# ArduBerry_5_0.net
KiCad netlist of a schematic drawn in EAGLE
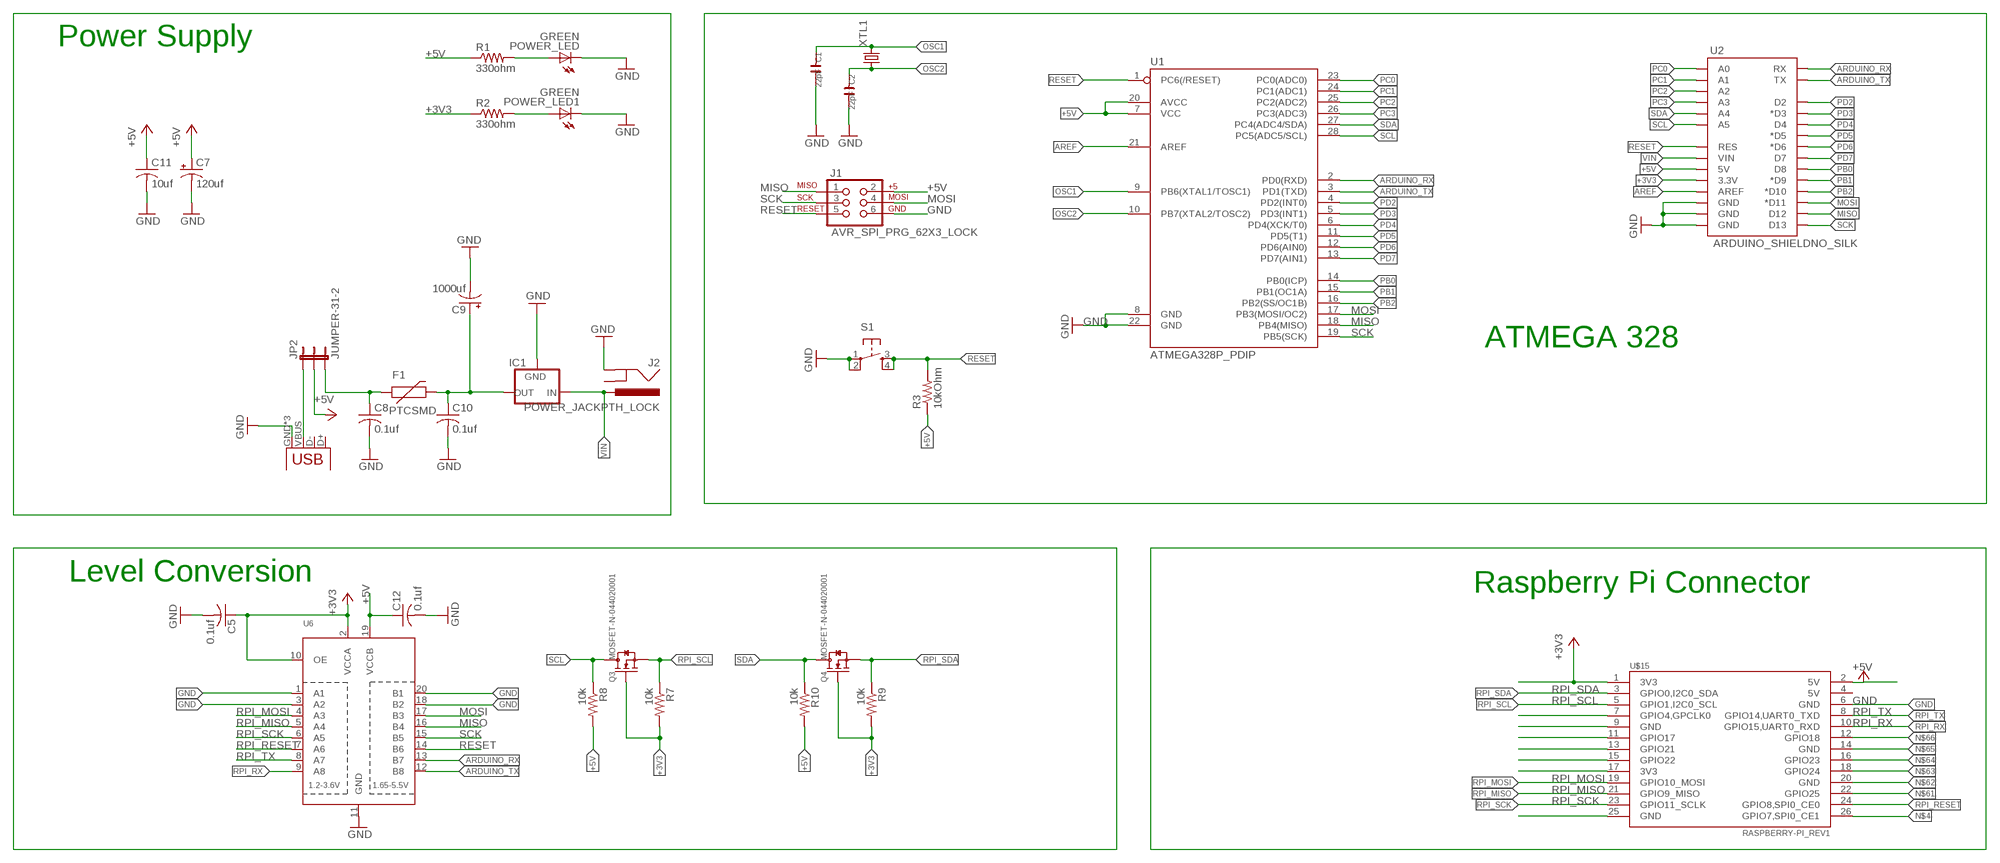
[diagram p0: schematic, sheet 1]

(export (version "E")
  (design (tool "Eeschema 10.0.6"))
  (components
    (comp (ref "C1")
      (value "22pF")
      (footprint "eagle-import:C0805")
      (libsource (lib "eagle-import") (part "C-0805"))
    )
    (comp (ref "C2")
      (value "22pF")
      (footprint "eagle-import:C0805")
      (libsource (lib "eagle-import") (part "C-0805"))
    )
    (comp (ref "C5")
      (value "0.1uf")
      (footprint "eagle-import:C0603")
      (libsource (lib "eagle-import") (part "resistor_C-USC0603"))
    )
    (comp (ref "C7")
      (value "120uf")
      (footprint "eagle-import:E2,5-6")
      (libsource (lib "eagle-import") (part "CPOL-USE2.5-6"))
    )
    (comp (ref "C8")
      (value "0.1uf")
      (footprint "eagle-import:C0603")
      (libsource (lib "eagle-import") (part "resistor_C-USC0603"))
    )
    (comp (ref "C9")
      (value "1000uf")
      (footprint "eagle-import:E3,5-10")
      (libsource (lib "eagle-import") (part "CPOL-USE3.5-10"))
    )
    (comp (ref "C10")
      (value "0.1uf")
      (footprint "eagle-import:C0603")
      (libsource (lib "eagle-import") (part "resistor_C-USC0603"))
    )
    (comp (ref "C11")
      (value "10uf")
      (footprint "eagle-import:C0805")
      (libsource (lib "eagle-import") (part "C-USC0805"))
    )
    (comp (ref "C12")
      (value "0.1uf")
      (footprint "eagle-import:C0603")
      (libsource (lib "eagle-import") (part "resistor_C-USC0603"))
    )
    (comp (ref "F1")
      (value "PTCSMD")
      (footprint "eagle-import:PTC-1206")
      (libsource (lib "eagle-import") (part "PTCSMD"))
    )
    (comp (ref "IC1")
      (value "V_REG_78XXSIDE")
      (footprint "eagle-import:78XXL")
      (libsource (lib "eagle-import") (part "V_REG_78XXSIDE"))
    )
    (comp (ref "J1")
      (value "AVR_SPI_PRG_62X3_LOCK")
      (footprint "eagle-import:2X3_LOCK")
      (libsource (lib "eagle-import") (part "AVR_SPI_PRG_62X3_LOCK"))
    )
    (comp (ref "J2")
      (value "POWER_JACKPTH_LOCK")
      (footprint "eagle-import:POWER_JACK_PTH_LOCK")
      (libsource (lib "eagle-import") (part "POWER_JACKPTH_LOCK"))
    )
    (comp (ref "JP1")
      (value "USB-MICROB")
      (footprint "eagle-import:USB-MICROB")
      (libsource (lib "eagle-import") (part "USB-MICROB"))
    )
    (comp (ref "JP2")
      (value "JUMPER-31-2")
      (footprint "eagle-import:SJ_3_PASTE1&2")
      (libsource (lib "eagle-import") (part "JUMPER-31-2"))
    )
    (comp (ref "POWER_LED")
      (value "GREEN")
      (footprint "eagle-import:LED-0603")
      (libsource (lib "eagle-import") (part "LED-GREEN0603"))
    )
    (comp (ref "POWER_LED1")
      (value "GREEN")
      (footprint "eagle-import:LED-0603")
      (libsource (lib "eagle-import") (part "LED-GREEN0603"))
    )
    (comp (ref "Q3")
      (value "MOSFET-N-044020001")
      (footprint "eagle-import:SOT23")
      (libsource (lib "eagle-import") (part "MOSFET-N-044020001"))
    )
    (comp (ref "Q4")
      (value "MOSFET-N-044020001")
      (footprint "eagle-import:SOT23")
      (libsource (lib "eagle-import") (part "MOSFET-N-044020001"))
    )
    (comp (ref "R1")
      (value "330ohm")
      (footprint "eagle-import:0603-RES")
      (libsource (lib "eagle-import") (part "RESISTOR0603"))
    )
    (comp (ref "R2")
      (value "330ohm")
      (footprint "eagle-import:0603-RES")
      (libsource (lib "eagle-import") (part "RESISTOR0603"))
    )
    (comp (ref "R3")
      (value "10kOhm")
      (footprint "eagle-import:0603-RES")
      (libsource (lib "eagle-import") (part "RESISTOR0603"))
    )
    (comp (ref "R7")
      (value "10k")
      (footprint "eagle-import:0603-RES")
      (libsource (lib "eagle-import") (part "RESISTOR0603"))
    )
    (comp (ref "R8")
      (value "10k")
      (footprint "eagle-import:0603-RES")
      (libsource (lib "eagle-import") (part "RESISTOR0603"))
    )
    (comp (ref "R9")
      (value "10k")
      (footprint "eagle-import:0603-RES")
      (libsource (lib "eagle-import") (part "RESISTOR0603"))
    )
    (comp (ref "R10")
      (value "10k")
      (footprint "eagle-import:0603-RES")
      (libsource (lib "eagle-import") (part "RESISTOR0603"))
    )
    (comp (ref "S1")
      (value "TAC_SWITCHPTH")
      (footprint "eagle-import:TACTILE-PTH")
      (libsource (lib "eagle-import") (part "TAC_SWITCHPTH"))
    )
    (comp (ref "U$15")
      (value "RASPBERRY-PI_REV1")
      (footprint "eagle-import:RASPBERRY-PI_REV1")
      (libsource (lib "eagle-import") (part "RASPBERRY-PI_REV1"))
    )
    (comp (ref "U1")
      (value "ATMEGA328P_PDIP")
      (footprint "eagle-import:DIL28-3")
      (libsource (lib "eagle-import") (part "ATMEGA328P_PDIP"))
    )
    (comp (ref "U2")
      (value "ARDUINO_SHIELDNO_SILK")
      (footprint "eagle-import:DUEMILANOVE_VIAS")
      (libsource (lib "eagle-import") (part "ARDUINO_SHIELDNO_SILK"))
    )
    (comp (ref "U6")
      (value "TXB0108PWR")
      (footprint "eagle-import:TSSOP20")
      (libsource (lib "eagle-import") (part "TXB0108PWR"))
    )
    (comp (ref "XTL1")
      (value "CRYSTALHC49S")
      (footprint "eagle-import:HC49_S")
      (libsource (lib "eagle-import") (part "CRYSTALHC49S"))
    )
  )
  (nets
    (net (code "1") (name "+3V3") (class "Default")
      (node (ref "C5") (pin "1") (pinfunction "1_1") (pintype "passive"))
      (node (ref "Q3") (pin "1") (pinfunction "G_1") (pintype "passive"))
      (node (ref "Q4") (pin "1") (pinfunction "G_1") (pintype "passive"))
      (node (ref "R2") (pin "1") (pinfunction "1_1") (pintype "passive"))
      (node (ref "R7") (pin "2") (pinfunction "2_2") (pintype "passive"))
      (node (ref "R9") (pin "2") (pinfunction "2_2") (pintype "passive"))
      (node (ref "U$15") (pin "1") (pinfunction "3V3_1") (pintype "bidirectional"))
      (node (ref "U2") (pin "3.3V") (pinfunction "3.3V_3.3V") (pintype "bidirectional"))
      (node (ref "U6") (pin "10") (pinfunction "OE_10") (pintype "bidirectional"))
      (node (ref "U6") (pin "2") (pinfunction "VCCA_2") (pintype "bidirectional"))
    )
    (net (code "2") (name "+5V") (class "Default")
      (node (ref "C11") (pin "1") (pinfunction "1_1") (pintype "passive"))
      (node (ref "C12") (pin "1") (pinfunction "1_1") (pintype "passive"))
      (node (ref "C7") (pin "+") (pinfunction "+_+") (pintype "passive"))
      (node (ref "J1") (pin "2") (pinfunction "2_2") (pintype "passive"))
      (node (ref "JP2") (pin "2") (pinfunction "2_2") (pintype "passive"))
      (node (ref "R1") (pin "1") (pinfunction "1_1") (pintype "passive"))
      (node (ref "R10") (pin "2") (pinfunction "2_2") (pintype "passive"))
      (node (ref "R3") (pin "1") (pinfunction "1_1") (pintype "passive"))
      (node (ref "R8") (pin "2") (pinfunction "2_2") (pintype "passive"))
      (node (ref "U$15") (pin "2") (pinfunction "5V_2") (pintype "bidirectional"))
      (node (ref "U1") (pin "20") (pinfunction "AVCC_20") (pintype "bidirectional"))
      (node (ref "U1") (pin "7") (pinfunction "VCC_7") (pintype "bidirectional"))
      (node (ref "U2") (pin "5V") (pinfunction "5V_5V") (pintype "bidirectional"))
      (node (ref "U6") (pin "19") (pinfunction "VCCB_19") (pintype "bidirectional"))
    )
    (net (code "3") (name "ARDUINO_RX") (class "Default")
      (node (ref "U1") (pin "2") (pinfunction "PD0(RXD)_2") (pintype "bidirectional"))
      (node (ref "U2") (pin "RX") (pinfunction "RX_RX") (pintype "bidirectional"))
      (node (ref "U6") (pin "13") (pinfunction "B7_13") (pintype "bidirectional"))
    )
    (net (code "4") (name "ARDUINO_TX") (class "Default")
      (node (ref "U1") (pin "3") (pinfunction "PD1(TXD)_3") (pintype "bidirectional"))
      (node (ref "U2") (pin "TX") (pinfunction "TX_TX") (pintype "bidirectional"))
      (node (ref "U6") (pin "12") (pinfunction "B8_12") (pintype "bidirectional"))
    )
    (net (code "5") (name "AREF") (class "Default")
      (node (ref "U1") (pin "21") (pinfunction "AREF_21") (pintype "bidirectional"))
      (node (ref "U2") (pin "AREF") (pinfunction "AREF_AREF") (pintype "bidirectional"))
    )
    (net (code "6") (name "GND") (class "Default")
      (node (ref "C1") (pin "2") (pinfunction "2_2") (pintype "bidirectional"))
      (node (ref "C10") (pin "2") (pinfunction "2_2") (pintype "passive"))
      (node (ref "C11") (pin "2") (pinfunction "2_2") (pintype "passive"))
      (node (ref "C12") (pin "2") (pinfunction "2_2") (pintype "passive"))
      (node (ref "C2") (pin "2") (pinfunction "2_2") (pintype "bidirectional"))
      (node (ref "C5") (pin "2") (pinfunction "2_2") (pintype "passive"))
      (node (ref "C7") (pin "-") (pinfunction "-_-") (pintype "passive"))
      (node (ref "C8") (pin "2") (pinfunction "2_2") (pintype "passive"))
      (node (ref "C9") (pin "-") (pinfunction "-_-") (pintype "passive"))
      (node (ref "IC1") (pin "GND") (pinfunction "GND_GND") (pintype "input"))
      (node (ref "J1") (pin "6") (pinfunction "6_6") (pintype "passive"))
      (node (ref "J2") (pin "GND") (pinfunction "GND_GND") (pintype "bidirectional"))
      (node (ref "JP1") (pin "GND") (pinfunction "GND_GND") (pintype "bidirectional"))
      (node (ref "JP1") (pin "MT1") (pinfunction "GND_MT1") (pintype "bidirectional"))
      (node (ref "JP1") (pin "MT2") (pinfunction "GND_MT2") (pintype "bidirectional"))
      (node (ref "POWER_LED") (pin "C") (pinfunction "C_C") (pintype "passive"))
      (node (ref "POWER_LED1") (pin "C") (pinfunction "C_C") (pintype "passive"))
      (node (ref "S1") (pin "1") (pinfunction "1_1") (pintype "passive"))
      (node (ref "S1") (pin "2") (pinfunction "2_2") (pintype "passive"))
      (node (ref "U$15") (pin "6") (pinfunction "GND_6") (pintype "bidirectional"))
      (node (ref "U1") (pin "22") (pinfunction "GND_22") (pintype "bidirectional"))
      (node (ref "U1") (pin "8") (pinfunction "GND_8") (pintype "bidirectional"))
      (node (ref "U2") (pin "GND@0") (pinfunction "GND_GND@0") (pintype "bidirectional"))
      (node (ref "U2") (pin "GND@1") (pinfunction "GND_GND@1") (pintype "bidirectional"))
      (node (ref "U2") (pin "GND@2") (pinfunction "GND_GND@2") (pintype "bidirectional"))
      (node (ref "U6") (pin "1") (pinfunction "A1_1") (pintype "bidirectional"))
      (node (ref "U6") (pin "11") (pinfunction "GND_11") (pintype "bidirectional"))
      (node (ref "U6") (pin "18") (pinfunction "B2_18") (pintype "bidirectional"))
      (node (ref "U6") (pin "20") (pinfunction "B1_20") (pintype "bidirectional"))
      (node (ref "U6") (pin "3") (pinfunction "A2_3") (pintype "bidirectional"))
    )
    (net (code "7") (name "MISO") (class "Default")
      (node (ref "J1") (pin "1") (pinfunction "1_1") (pintype "passive"))
      (node (ref "U1") (pin "18") (pinfunction "PB4(MISO)_18") (pintype "bidirectional"))
      (node (ref "U2") (pin "D12") (pinfunction "D12_D12") (pintype "bidirectional"))
      (node (ref "U6") (pin "16") (pinfunction "B4_16") (pintype "bidirectional"))
    )
    (net (code "8") (name "MOSI") (class "Default")
      (node (ref "J1") (pin "4") (pinfunction "4_4") (pintype "passive"))
      (node (ref "U1") (pin "17") (pinfunction "PB3(MOSI/OC2)_17") (pintype "bidirectional"))
      (node (ref "U2") (pin "D11") (pinfunction "*D11_D11") (pintype "bidirectional"))
      (node (ref "U6") (pin "17") (pinfunction "B3_17") (pintype "bidirectional"))
    )
    (net (code "9") (name "N$4") (class "Default")
      (node (ref "U$15") (pin "26") (pinfunction "GPIO7,SPI0_CE1_26") (pintype "bidirectional"))
    )
    (net (code "10") (name "N$61") (class "Default")
      (node (ref "U$15") (pin "22") (pinfunction "GPIO25_22") (pintype "bidirectional"))
    )
    (net (code "11") (name "N$62") (class "Default")
      (node (ref "U$15") (pin "20") (pinfunction "GND_20") (pintype "bidirectional"))
    )
    (net (code "12") (name "N$63") (class "Default")
      (node (ref "U$15") (pin "18") (pinfunction "GPIO24_18") (pintype "bidirectional"))
    )
    (net (code "13") (name "N$64") (class "Default")
      (node (ref "U$15") (pin "16") (pinfunction "GPIO23_16") (pintype "bidirectional"))
    )
    (net (code "14") (name "N$65") (class "Default")
      (node (ref "U$15") (pin "14") (pinfunction "GND_14") (pintype "bidirectional"))
    )
    (net (code "15") (name "N$66") (class "Default")
      (node (ref "U$15") (pin "12") (pinfunction "GPIO18_12") (pintype "bidirectional"))
    )
    (net (code "16") (name "Net-(C8-Pad1)") (class "Default")
      (node (ref "C8") (pin "1") (pinfunction "1_1") (pintype "passive"))
      (node (ref "F1") (pin "1") (pinfunction "1_1") (pintype "bidirectional"))
      (node (ref "JP2") (pin "3") (pinfunction "3_3") (pintype "passive"))
    )
    (net (code "17") (name "Net-(C10-Pad1)") (class "Default")
      (node (ref "C10") (pin "1") (pinfunction "1_1") (pintype "passive"))
      (node (ref "C9") (pin "+") (pinfunction "+_+") (pintype "passive"))
      (node (ref "F1") (pin "2") (pinfunction "2_2") (pintype "bidirectional"))
      (node (ref "IC1") (pin "OUT") (pinfunction "OUT_OUT") (pintype "output"))
    )
    (net (code "18") (name "Net-(JP1-PadVBUS)") (class "Default")
      (node (ref "JP1") (pin "VBUS") (pinfunction "VBUS_VBUS") (pintype "bidirectional"))
      (node (ref "JP2") (pin "1") (pinfunction "1_1") (pintype "passive"))
    )
    (net (code "19") (name "Net-(POWER_LED-PadA)") (class "Default")
      (node (ref "POWER_LED") (pin "A") (pinfunction "A_A") (pintype "passive"))
      (node (ref "R1") (pin "2") (pinfunction "2_2") (pintype "passive"))
    )
    (net (code "20") (name "Net-(POWER_LED1-PadA)") (class "Default")
      (node (ref "POWER_LED1") (pin "A") (pinfunction "A_A") (pintype "passive"))
      (node (ref "R2") (pin "2") (pinfunction "2_2") (pintype "passive"))
    )
    (net (code "21") (name "OSC1") (class "Default")
      (node (ref "C1") (pin "1") (pinfunction "1_1") (pintype "bidirectional"))
      (node (ref "U1") (pin "9") (pinfunction "PB6(XTAL1/TOSC1)_9") (pintype "bidirectional"))
      (node (ref "XTL1") (pin "2") (pinfunction "2_2") (pintype "passive"))
    )
    (net (code "22") (name "OSC2") (class "Default")
      (node (ref "C2") (pin "1") (pinfunction "1_1") (pintype "bidirectional"))
      (node (ref "U1") (pin "10") (pinfunction "PB7(XTAL2/TOSC2)_10") (pintype "bidirectional"))
      (node (ref "XTL1") (pin "1") (pinfunction "1_1") (pintype "passive"))
    )
    (net (code "23") (name "PB0") (class "Default")
      (node (ref "U1") (pin "14") (pinfunction "PB0(ICP)_14") (pintype "bidirectional"))
      (node (ref "U2") (pin "D8") (pinfunction "D8_D8") (pintype "bidirectional"))
    )
    (net (code "24") (name "PB1") (class "Default")
      (node (ref "U1") (pin "15") (pinfunction "PB1(OC1A)_15") (pintype "bidirectional"))
      (node (ref "U2") (pin "D9") (pinfunction "*D9_D9") (pintype "bidirectional"))
    )
    (net (code "25") (name "PB2") (class "Default")
      (node (ref "U1") (pin "16") (pinfunction "PB2(SS/OC1B)_16") (pintype "bidirectional"))
      (node (ref "U2") (pin "D10") (pinfunction "*D10_D10") (pintype "bidirectional"))
    )
    (net (code "26") (name "PC0") (class "Default")
      (node (ref "U1") (pin "23") (pinfunction "PC0(ADC0)_23") (pintype "bidirectional"))
      (node (ref "U2") (pin "A0") (pinfunction "A0_A0") (pintype "bidirectional"))
    )
    (net (code "27") (name "PC1") (class "Default")
      (node (ref "U1") (pin "24") (pinfunction "PC1(ADC1)_24") (pintype "bidirectional"))
      (node (ref "U2") (pin "A1") (pinfunction "A1_A1") (pintype "bidirectional"))
    )
    (net (code "28") (name "PC2") (class "Default")
      (node (ref "U1") (pin "25") (pinfunction "PC2(ADC2)_25") (pintype "bidirectional"))
      (node (ref "U2") (pin "A2") (pinfunction "A2_A2") (pintype "bidirectional"))
    )
    (net (code "29") (name "PC3") (class "Default")
      (node (ref "U1") (pin "26") (pinfunction "PC3(ADC3)_26") (pintype "bidirectional"))
      (node (ref "U2") (pin "A3") (pinfunction "A3_A3") (pintype "bidirectional"))
    )
    (net (code "30") (name "PD2") (class "Default")
      (node (ref "U1") (pin "4") (pinfunction "PD2(INT0)_4") (pintype "bidirectional"))
      (node (ref "U2") (pin "D2") (pinfunction "D2_D2") (pintype "bidirectional"))
    )
    (net (code "31") (name "PD3") (class "Default")
      (node (ref "U1") (pin "5") (pinfunction "PD3(INT1)_5") (pintype "bidirectional"))
      (node (ref "U2") (pin "D3") (pinfunction "*D3_D3") (pintype "bidirectional"))
    )
    (net (code "32") (name "PD4") (class "Default")
      (node (ref "U1") (pin "6") (pinfunction "PD4(XCK/T0)_6") (pintype "bidirectional"))
      (node (ref "U2") (pin "D4") (pinfunction "D4_D4") (pintype "bidirectional"))
    )
    (net (code "33") (name "PD5") (class "Default")
      (node (ref "U1") (pin "11") (pinfunction "PD5(T1)_11") (pintype "bidirectional"))
      (node (ref "U2") (pin "D5") (pinfunction "*D5_D5") (pintype "bidirectional"))
    )
    (net (code "34") (name "PD6") (class "Default")
      (node (ref "U1") (pin "12") (pinfunction "PD6(AIN0)_12") (pintype "bidirectional"))
      (node (ref "U2") (pin "D6") (pinfunction "*D6_D6") (pintype "bidirectional"))
    )
    (net (code "35") (name "PD7") (class "Default")
      (node (ref "U1") (pin "13") (pinfunction "PD7(AIN1)_13") (pintype "bidirectional"))
      (node (ref "U2") (pin "D7") (pinfunction "D7_D7") (pintype "bidirectional"))
    )
    (net (code "36") (name "RESET") (class "Default")
      (node (ref "J1") (pin "5") (pinfunction "5_5") (pintype "passive"))
      (node (ref "R3") (pin "2") (pinfunction "2_2") (pintype "passive"))
      (node (ref "S1") (pin "3") (pinfunction "3_3") (pintype "passive"))
      (node (ref "S1") (pin "4") (pinfunction "4_4") (pintype "passive"))
      (node (ref "U1") (pin "1") (pinfunction "PC6(/RESET)_1") (pintype "bidirectional"))
      (node (ref "U2") (pin "RES") (pinfunction "RES_RES") (pintype "bidirectional"))
      (node (ref "U6") (pin "14") (pinfunction "B6_14") (pintype "bidirectional"))
    )
    (net (code "37") (name "RPI_MISO") (class "Default")
      (node (ref "U$15") (pin "21") (pinfunction "GPIO9_MISO_21") (pintype "bidirectional"))
      (node (ref "U6") (pin "5") (pinfunction "A4_5") (pintype "bidirectional"))
    )
    (net (code "38") (name "RPI_MOSI") (class "Default")
      (node (ref "U$15") (pin "19") (pinfunction "GPIO10_MOSI_19") (pintype "bidirectional"))
      (node (ref "U6") (pin "4") (pinfunction "A3_4") (pintype "bidirectional"))
    )
    (net (code "39") (name "RPI_RESET") (class "Default")
      (node (ref "U$15") (pin "24") (pinfunction "GPIO8,SPI0_CE0_24") (pintype "bidirectional"))
      (node (ref "U6") (pin "7") (pinfunction "A6_7") (pintype "bidirectional"))
    )
    (net (code "40") (name "RPI_RX") (class "Default")
      (node (ref "U$15") (pin "10") (pinfunction "GPIO15,UART0_RXD_10") (pintype "bidirectional"))
      (node (ref "U6") (pin "9") (pinfunction "A8_9") (pintype "bidirectional"))
    )
    (net (code "41") (name "RPI_SCK") (class "Default")
      (node (ref "U$15") (pin "23") (pinfunction "GPIO11_SCLK_23") (pintype "bidirectional"))
      (node (ref "U6") (pin "6") (pinfunction "A5_6") (pintype "bidirectional"))
    )
    (net (code "42") (name "RPI_SCL") (class "Default")
      (node (ref "Q3") (pin "2") (pinfunction "S_2") (pintype "passive"))
      (node (ref "R7") (pin "1") (pinfunction "1_1") (pintype "passive"))
      (node (ref "U$15") (pin "5") (pinfunction "GPIO1,I2C0_SCL_5") (pintype "bidirectional"))
    )
    (net (code "43") (name "RPI_SDA") (class "Default")
      (node (ref "Q4") (pin "2") (pinfunction "S_2") (pintype "passive"))
      (node (ref "R9") (pin "1") (pinfunction "1_1") (pintype "passive"))
      (node (ref "U$15") (pin "3") (pinfunction "GPIO0,I2C0_SDA_3") (pintype "bidirectional"))
    )
    (net (code "44") (name "RPI_TX") (class "Default")
      (node (ref "U$15") (pin "8") (pinfunction "GPIO14,UART0_TXD_8") (pintype "bidirectional"))
      (node (ref "U6") (pin "8") (pinfunction "A7_8") (pintype "bidirectional"))
    )
    (net (code "45") (name "SCK") (class "Default")
      (node (ref "J1") (pin "3") (pinfunction "3_3") (pintype "passive"))
      (node (ref "U1") (pin "19") (pinfunction "PB5(SCK)_19") (pintype "bidirectional"))
      (node (ref "U2") (pin "D13") (pinfunction "D13_D13") (pintype "bidirectional"))
      (node (ref "U6") (pin "15") (pinfunction "B5_15") (pintype "bidirectional"))
    )
    (net (code "46") (name "SCL") (class "Default")
      (node (ref "Q3") (pin "3") (pinfunction "D_3") (pintype "passive"))
      (node (ref "R8") (pin "1") (pinfunction "1_1") (pintype "passive"))
      (node (ref "U1") (pin "28") (pinfunction "PC5(ADC5/SCL)_28") (pintype "bidirectional"))
      (node (ref "U2") (pin "A5") (pinfunction "A5_A5") (pintype "bidirectional"))
    )
    (net (code "47") (name "SDA") (class "Default")
      (node (ref "Q4") (pin "3") (pinfunction "D_3") (pintype "passive"))
      (node (ref "R10") (pin "1") (pinfunction "1_1") (pintype "passive"))
      (node (ref "U1") (pin "27") (pinfunction "PC4(ADC4/SDA)_27") (pintype "bidirectional"))
      (node (ref "U2") (pin "A4") (pinfunction "A4_A4") (pintype "bidirectional"))
    )
    (net (code "48") (name "VIN") (class "Default")
      (node (ref "IC1") (pin "IN") (pinfunction "IN_IN") (pintype "input"))
      (node (ref "J2") (pin "PWR") (pinfunction "PWR_PWR") (pintype "bidirectional"))
      (node (ref "U2") (pin "VIN") (pinfunction "VIN_VIN") (pintype "bidirectional"))
    )
    (net (code "49") (name "unconnected-(J2-PadGNDBREAK)") (class "Default")
      (node (ref "J2") (pin "GNDBREAK") (pinfunction "GNDBREAK_GNDBREAK") (pintype "bidirectional"))
    )
    (net (code "50") (name "unconnected-(JP1-PadD+)") (class "Default")
      (node (ref "JP1") (pin "D+") (pinfunction "D+_D+") (pintype "bidirectional"))
    )
    (net (code "51") (name "unconnected-(JP1-PadD-)") (class "Default")
      (node (ref "JP1") (pin "D-") (pinfunction "D-_D-") (pintype "bidirectional"))
    )
    (net (code "52") (name "unconnected-(U$15-3V3-Pad17)") (class "Default")
      (node (ref "U$15") (pin "17") (pinfunction "3V3_17") (pintype "bidirectional"))
    )
    (net (code "53") (name "unconnected-(U$15-5V-Pad4)") (class "Default")
      (node (ref "U$15") (pin "4") (pinfunction "5V_4") (pintype "bidirectional"))
    )
    (net (code "54") (name "unconnected-(U$15-GND-Pad9)") (class "Default")
      (node (ref "U$15") (pin "9") (pinfunction "GND_9") (pintype "bidirectional"))
    )
    (net (code "55") (name "unconnected-(U$15-GND-Pad25)") (class "Default")
      (node (ref "U$15") (pin "25") (pinfunction "GND_25") (pintype "bidirectional"))
    )
    (net (code "56") (name "unconnected-(U$15-GPIO4,GPCLK0-Pad7)") (class "Default")
      (node (ref "U$15") (pin "7") (pinfunction "GPIO4,GPCLK0_7") (pintype "bidirectional"))
    )
    (net (code "57") (name "unconnected-(U$15-GPIO17-Pad11)") (class "Default")
      (node (ref "U$15") (pin "11") (pinfunction "GPIO17_11") (pintype "bidirectional"))
    )
    (net (code "58") (name "unconnected-(U$15-GPIO21-Pad13)") (class "Default")
      (node (ref "U$15") (pin "13") (pinfunction "GPIO21_13") (pintype "bidirectional"))
    )
    (net (code "59") (name "unconnected-(U$15-GPIO22-Pad15)") (class "Default")
      (node (ref "U$15") (pin "15") (pinfunction "GPIO22_15") (pintype "bidirectional"))
    )
  )
)
